# GbEthernet.net
KiCad netlist of a schematic drawn in Altium Designer
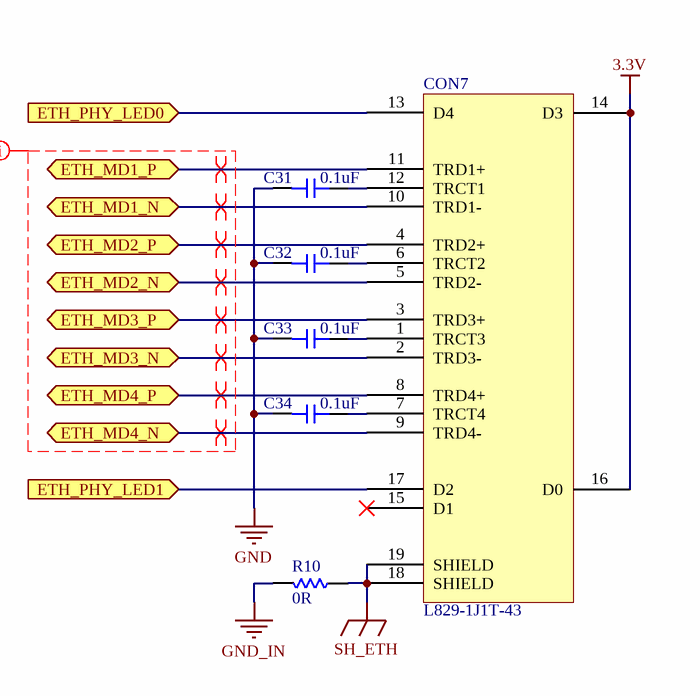
[diagram p0: GbEthernet.SchDoc]

(export (version "E")
  (design (tool "Eeschema 10.0.6"))
  (components
    (comp (ref "C31")
      (value "0.1uF")
      (footprint "0603-CAP")
      (description "Capacitor")
      (libsource (lib "AMDC") (part "Capacitor"))
    )
    (comp (ref "C32")
      (value "0.1uF")
      (footprint "0603-CAP")
      (description "Capacitor")
      (libsource (lib "AMDC") (part "Capacitor"))
    )
    (comp (ref "C33")
      (value "0.1uF")
      (footprint "0603-CAP")
      (description "Capacitor")
      (libsource (lib "AMDC") (part "Capacitor"))
    )
    (comp (ref "C34")
      (value "0.1uF")
      (footprint "0603-CAP")
      (description "Capacitor")
      (libsource (lib "AMDC") (part "Capacitor"))
    )
    (comp (ref "CON7")
      (value "L829-1J1T-43")
      (footprint "L829-1J1T-43")
      (libsource (lib "AMDC") (part "L829-1J1T-43"))
    )
    (comp (ref "R10")
      (value "0R")
      (footprint "1206-RES")
      (description "Resistor")
      (libsource (lib "AMDC") (part "Resistor"))
    )
  )
  (nets
    (net (code "1") (name "/ETH_MD1_N") (class "Default")
      (node (ref "CON7") (pin "10") (pinfunction "TRD1-_10") (pintype "passive"))
    )
    (net (code "2") (name "/ETH_MD1_P") (class "Default")
      (node (ref "CON7") (pin "11") (pinfunction "TRD1+_11") (pintype "passive"))
    )
    (net (code "3") (name "/ETH_MD2_N") (class "Default")
      (node (ref "CON7") (pin "5") (pinfunction "TRD2-_5") (pintype "passive"))
    )
    (net (code "4") (name "/ETH_MD2_P") (class "Default")
      (node (ref "CON7") (pin "4") (pinfunction "TRD2+_4") (pintype "passive"))
    )
    (net (code "5") (name "/ETH_MD3_N") (class "Default")
      (node (ref "CON7") (pin "2") (pinfunction "TRD3-_2") (pintype "passive"))
    )
    (net (code "6") (name "/ETH_MD3_P") (class "Default")
      (node (ref "CON7") (pin "3") (pinfunction "TRD3+_3") (pintype "passive"))
    )
    (net (code "7") (name "/ETH_MD4_N") (class "Default")
      (node (ref "CON7") (pin "9") (pinfunction "TRD4-_9") (pintype "passive"))
    )
    (net (code "8") (name "/ETH_MD4_P") (class "Default")
      (node (ref "CON7") (pin "8") (pinfunction "TRD4+_8") (pintype "passive"))
    )
    (net (code "9") (name "/ETH_PHY_LED0") (class "Default")
      (node (ref "CON7") (pin "13") (pinfunction "D4_13") (pintype "passive"))
    )
    (net (code "10") (name "/ETH_PHY_LED1") (class "Default")
      (node (ref "CON7") (pin "17") (pinfunction "D2_17") (pintype "passive"))
    )
    (net (code "11") (name "3.3V") (class "Default")
      (node (ref "CON7") (pin "14") (pinfunction "D3_14") (pintype "passive"))
      (node (ref "CON7") (pin "16") (pinfunction "D0_16") (pintype "passive"))
    )
    (net (code "12") (name "GND") (class "Default")
      (node (ref "C31") (pin "1") (pinfunction "1_1") (pintype "passive"))
      (node (ref "C32") (pin "1") (pinfunction "1_1") (pintype "passive"))
      (node (ref "C33") (pin "1") (pinfunction "1_1") (pintype "passive"))
      (node (ref "C34") (pin "1") (pinfunction "1_1") (pintype "passive"))
    )
    (net (code "13") (name "GND_IN") (class "Default")
      (node (ref "R10") (pin "2") (pinfunction "2_2") (pintype "passive"))
    )
    (net (code "14") (name "Net-(CON7-TRCT1)") (class "Default")
      (node (ref "C31") (pin "2") (pinfunction "2_2") (pintype "passive"))
      (node (ref "CON7") (pin "12") (pinfunction "TRCT1_12") (pintype "passive"))
    )
    (net (code "15") (name "Net-(CON7-TRCT2)") (class "Default")
      (node (ref "C32") (pin "2") (pinfunction "2_2") (pintype "passive"))
      (node (ref "CON7") (pin "6") (pinfunction "TRCT2_6") (pintype "passive"))
    )
    (net (code "16") (name "Net-(CON7-TRCT3)") (class "Default")
      (node (ref "C33") (pin "2") (pinfunction "2_2") (pintype "passive"))
      (node (ref "CON7") (pin "1") (pinfunction "TRCT3_1") (pintype "passive"))
    )
    (net (code "17") (name "Net-(CON7-TRCT4)") (class "Default")
      (node (ref "C34") (pin "2") (pinfunction "2_2") (pintype "passive"))
      (node (ref "CON7") (pin "7") (pinfunction "TRCT4_7") (pintype "passive"))
    )
    (net (code "18") (name "SH_ETH") (class "Default")
      (node (ref "CON7") (pin "18") (pinfunction "SHIELD_18") (pintype "passive"))
      (node (ref "CON7") (pin "19") (pinfunction "SHIELD_19") (pintype "passive"))
      (node (ref "R10") (pin "1") (pinfunction "1_1") (pintype "passive"))
    )
    (net (code "19") (name "unconnected-(CON7-D1-Pad15)") (class "Default")
      (node (ref "CON7") (pin "15") (pinfunction "D1_15") (pintype "passive+no_connect"))
    )
  )
)
